# untitled.net
KiCad netlist of a schematic drawn in EAGLE
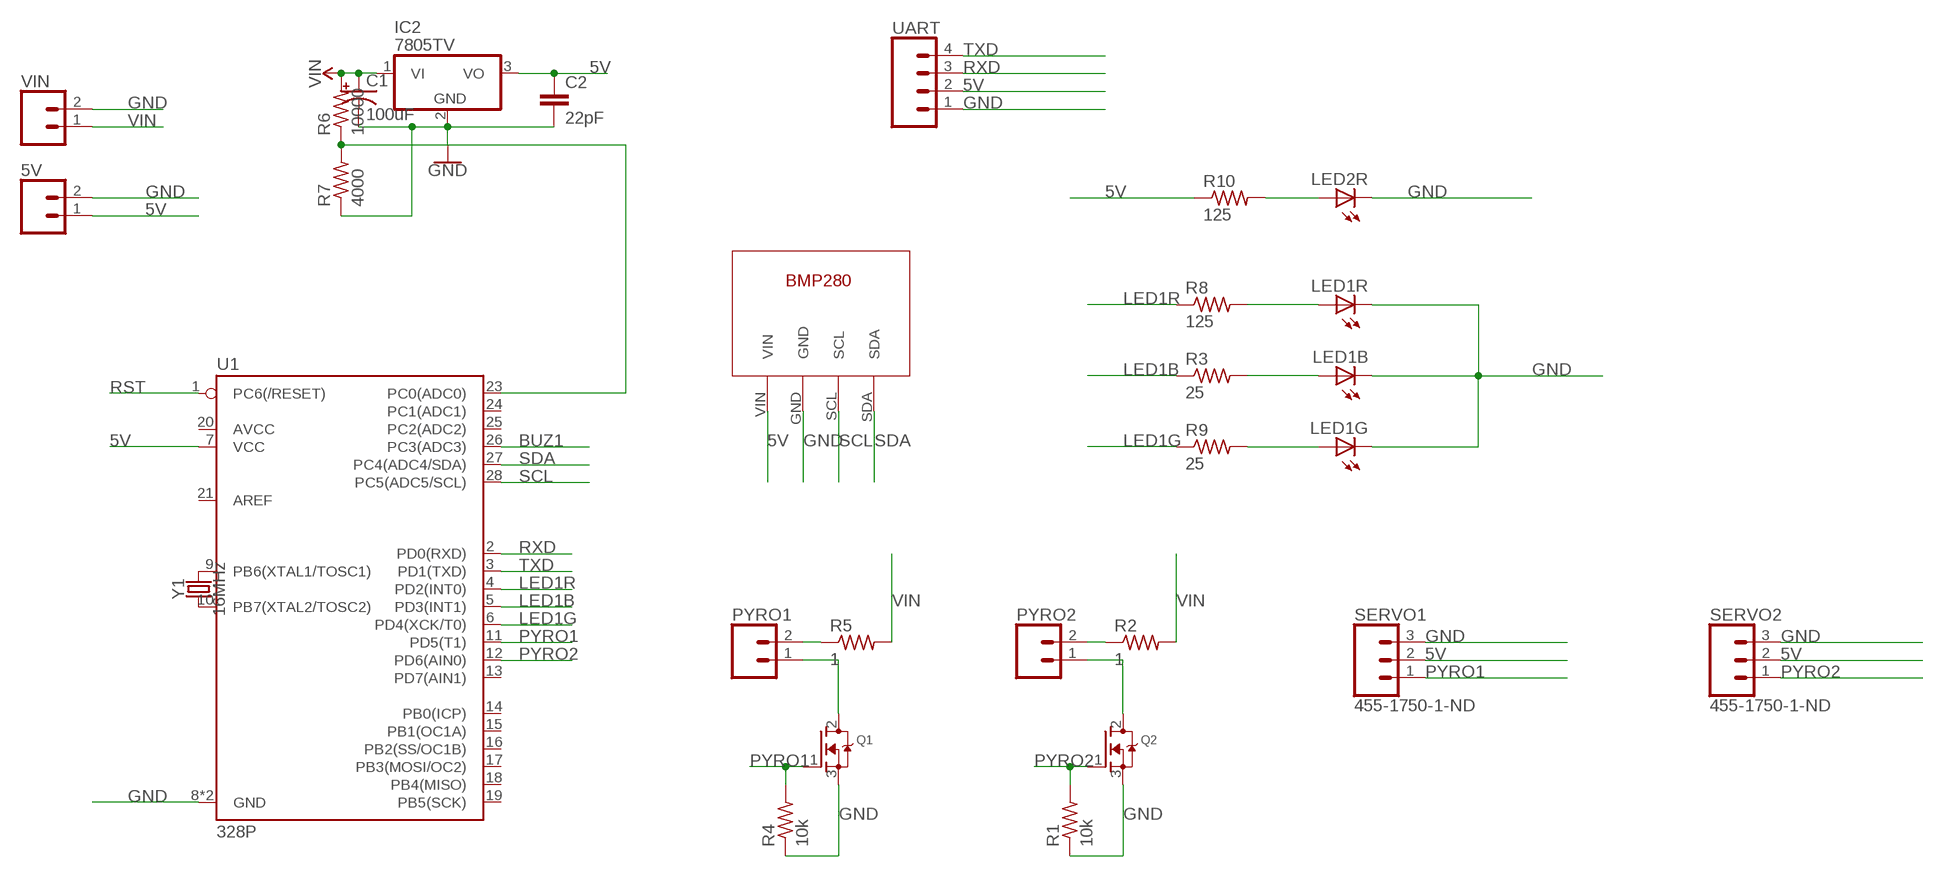
[diagram p0: schematic, sheet 1]

(export (version "E")
  (design (tool "Eeschema 10.0.6"))
  (components
    (comp (ref "5V")
      (value "CONN_02")
      (footprint "eagle-import:1X02")
      (libsource (lib "eagle-import") (part "CONN_02"))
    )
    (comp (ref "C1")
      (value "100uF")
      (footprint "eagle-import:CPOL-RADIAL-2.5MM-6.5MM")
      (libsource (lib "eagle-import") (part "100UF-POLAR-RADIAL-2.5MM-25V-20%"))
    )
    (comp (ref "C2")
      (value "22pF")
      (footprint "eagle-import:CAP-PTH-2.54")
      (libsource (lib "eagle-import") (part "22PF-PTH-2.54MM-200V-5%"))
    )
    (comp (ref "IC2")
      (value "7805TV")
      (footprint "eagle-import:TO220V")
      (libsource (lib "eagle-import") (part "78TV05"))
    )
    (comp (ref "LED1B")
      (value "LED1B")
      (footprint "eagle-import:LED5MM")
      (libsource (lib "eagle-import") (part "LED5MM"))
    )
    (comp (ref "LED1G")
      (value "LED1G")
      (footprint "eagle-import:LED5MM")
      (libsource (lib "eagle-import") (part "LED5MM"))
    )
    (comp (ref "LED1R")
      (value "LED1R")
      (footprint "eagle-import:LED5MM")
      (libsource (lib "eagle-import") (part "LED5MM"))
    )
    (comp (ref "LED2R")
      (value "LED1R")
      (footprint "eagle-import:LED5MM")
      (libsource (lib "eagle-import") (part "LED5MM"))
    )
    (comp (ref "PYRO1")
      (value "CONN_02")
      (footprint "eagle-import:1X02")
      (libsource (lib "eagle-import") (part "SparkFun-Connectors_513_CONN_02"))
    )
    (comp (ref "PYRO2")
      (value "CONN_02")
      (footprint "eagle-import:1X02")
      (libsource (lib "eagle-import") (part "SparkFun-Connectors_513_CONN_02"))
    )
    (comp (ref "Q1")
      (value "MOSFET-NGDS_TO220V")
      (footprint "eagle-import:TO220V")
      (libsource (lib "eagle-import") (part "MOSFET-NGDS_TO220V"))
    )
    (comp (ref "Q2")
      (value "MOSFET-NGDS_TO220V")
      (footprint "eagle-import:TO220V")
      (libsource (lib "eagle-import") (part "MOSFET-NGDS_TO220V"))
    )
    (comp (ref "R1")
      (value "10k")
      (footprint "eagle-import:0805-THM")
      (libsource (lib "eagle-import") (part "FLIPFLOP-RES"))
    )
    (comp (ref "R2")
      (value "1")
      (footprint "eagle-import:0805-THM")
      (libsource (lib "eagle-import") (part "FLIPFLOP-RES"))
    )
    (comp (ref "R3")
      (value "25")
      (footprint "eagle-import:0805-THM")
      (libsource (lib "eagle-import") (part "FLIPFLOP-RES"))
    )
    (comp (ref "R4")
      (value "10k")
      (footprint "eagle-import:0805-THM")
      (libsource (lib "eagle-import") (part "FLIPFLOP-RES"))
    )
    (comp (ref "R5")
      (value "1")
      (footprint "eagle-import:0805-THM")
      (libsource (lib "eagle-import") (part "FLIPFLOP-RES"))
    )
    (comp (ref "R6")
      (value "10000")
      (footprint "eagle-import:0805-THM")
      (libsource (lib "eagle-import") (part "FLIPFLOP-RES"))
    )
    (comp (ref "R7")
      (value "4000")
      (footprint "eagle-import:0805-THM")
      (libsource (lib "eagle-import") (part "FLIPFLOP-RES"))
    )
    (comp (ref "R8")
      (value "125")
      (footprint "eagle-import:0805-THM")
      (libsource (lib "eagle-import") (part "FLIPFLOP-RES"))
    )
    (comp (ref "R9")
      (value "25")
      (footprint "eagle-import:0805-THM")
      (libsource (lib "eagle-import") (part "FLIPFLOP-RES"))
    )
    (comp (ref "R10")
      (value "125")
      (footprint "eagle-import:0805-THM")
      (libsource (lib "eagle-import") (part "FLIPFLOP-RES"))
    )
    (comp (ref "SERVO1")
      (value "455-1750-1-ND")
      (footprint "eagle-import:1X03")
      (libsource (lib "eagle-import") (part "CONN_03"))
    )
    (comp (ref "SERVO2")
      (value "455-1750-1-ND")
      (footprint "eagle-import:1X03")
      (libsource (lib "eagle-import") (part "CONN_03"))
    )
    (comp (ref "U$1")
      (value "BMP280")
      (footprint "eagle-import:BMP280")
      (libsource (lib "eagle-import") (part "BMP280"))
    )
    (comp (ref "U1")
      (value "328P")
      (footprint "eagle-import:DIP28")
      (libsource (lib "eagle-import") (part "ATMEGA328P_PDIP"))
    )
    (comp (ref "UART")
      (value "CONN_04PTH")
      (footprint "eagle-import:1X04")
      (libsource (lib "eagle-import") (part "CONN_04PTH"))
    )
    (comp (ref "VIN")
      (value "CONN_02")
      (footprint "eagle-import:1X02")
      (libsource (lib "eagle-import") (part "CONN_02"))
    )
    (comp (ref "Y1")
      (value "16MHz")
      (footprint "eagle-import:HC49US")
      (libsource (lib "eagle-import") (part "CRYSTAL-16MHZPTH-HC49US"))
    )
  )
  (nets
    (net (code "1") (name "/5V") (class "Default")
      (node (ref "5V") (pin "1") (pinfunction "1_1") (pintype "passive"))
      (node (ref "C2") (pin "1") (pinfunction "1_1") (pintype "passive"))
      (node (ref "IC2") (pin "3") (pinfunction "VO_3") (pintype "passive"))
      (node (ref "R10") (pin "1") (pinfunction "1_1") (pintype "passive"))
      (node (ref "SERVO1") (pin "2") (pinfunction "2_2") (pintype "passive"))
      (node (ref "SERVO2") (pin "2") (pinfunction "2_2") (pintype "passive"))
      (node (ref "U$1") (pin "VIN") (pinfunction "VIN_VIN") (pintype "bidirectional"))
      (node (ref "U1") (pin "7") (pinfunction "VCC_7") (pintype "bidirectional"))
      (node (ref "UART") (pin "2") (pinfunction "2_2") (pintype "passive"))
    )
    (net (code "2") (name "/BUZ1") (class "Default")
      (node (ref "U1") (pin "26") (pinfunction "PC3(ADC3)_26") (pintype "bidirectional"))
    )
    (net (code "3") (name "/LED1B") (class "Default")
      (node (ref "R3") (pin "1") (pinfunction "1_1") (pintype "passive"))
      (node (ref "U1") (pin "5") (pinfunction "PD3(INT1)_5") (pintype "bidirectional"))
    )
    (net (code "4") (name "/LED1G") (class "Default")
      (node (ref "R9") (pin "1") (pinfunction "1_1") (pintype "passive"))
      (node (ref "U1") (pin "6") (pinfunction "PD4(XCK/T0)_6") (pintype "bidirectional"))
    )
    (net (code "5") (name "/LED1R") (class "Default")
      (node (ref "R8") (pin "1") (pinfunction "1_1") (pintype "passive"))
      (node (ref "U1") (pin "4") (pinfunction "PD2(INT0)_4") (pintype "bidirectional"))
    )
    (net (code "6") (name "/PYRO1") (class "Default")
      (node (ref "Q1") (pin "1") (pinfunction "G_1") (pintype "bidirectional"))
      (node (ref "R4") (pin "2") (pinfunction "2_2") (pintype "passive"))
      (node (ref "SERVO1") (pin "1") (pinfunction "1_1") (pintype "passive"))
      (node (ref "U1") (pin "11") (pinfunction "PD5(T1)_11") (pintype "bidirectional"))
    )
    (net (code "7") (name "/PYRO2") (class "Default")
      (node (ref "Q2") (pin "1") (pinfunction "G_1") (pintype "bidirectional"))
      (node (ref "R1") (pin "2") (pinfunction "2_2") (pintype "passive"))
      (node (ref "SERVO2") (pin "1") (pinfunction "1_1") (pintype "passive"))
      (node (ref "U1") (pin "12") (pinfunction "PD6(AIN0)_12") (pintype "bidirectional"))
    )
    (net (code "8") (name "/RST") (class "Default")
      (node (ref "U1") (pin "1") (pinfunction "PC6(/RESET)_1") (pintype "bidirectional"))
    )
    (net (code "9") (name "/RXD") (class "Default")
      (node (ref "U1") (pin "2") (pinfunction "PD0(RXD)_2") (pintype "bidirectional"))
      (node (ref "UART") (pin "3") (pinfunction "3_3") (pintype "passive"))
    )
    (net (code "10") (name "/SCL") (class "Default")
      (node (ref "U$1") (pin "SCL") (pinfunction "SCL_SCL") (pintype "bidirectional"))
      (node (ref "U1") (pin "28") (pinfunction "PC5(ADC5/SCL)_28") (pintype "bidirectional"))
    )
    (net (code "11") (name "/SDA") (class "Default")
      (node (ref "U$1") (pin "SDA") (pinfunction "SDA_SDA") (pintype "bidirectional"))
      (node (ref "U1") (pin "27") (pinfunction "PC4(ADC4/SDA)_27") (pintype "bidirectional"))
    )
    (net (code "12") (name "/TXD") (class "Default")
      (node (ref "U1") (pin "3") (pinfunction "PD1(TXD)_3") (pintype "bidirectional"))
      (node (ref "UART") (pin "4") (pinfunction "4_4") (pintype "passive"))
    )
    (net (code "13") (name "GND") (class "Default")
      (node (ref "5V") (pin "2") (pinfunction "2_2") (pintype "passive"))
      (node (ref "C1") (pin "2") (pinfunction "-_2") (pintype "passive"))
      (node (ref "C2") (pin "2") (pinfunction "2_2") (pintype "passive"))
      (node (ref "IC2") (pin "2") (pinfunction "GND_2") (pintype "passive"))
      (node (ref "LED1B") (pin "K") (pinfunction "C_K") (pintype "passive"))
      (node (ref "LED1G") (pin "K") (pinfunction "C_K") (pintype "passive"))
      (node (ref "LED1R") (pin "K") (pinfunction "C_K") (pintype "passive"))
      (node (ref "LED2R") (pin "K") (pinfunction "C_K") (pintype "passive"))
      (node (ref "Q1") (pin "3") (pinfunction "S_3") (pintype "bidirectional"))
      (node (ref "Q2") (pin "3") (pinfunction "S_3") (pintype "bidirectional"))
      (node (ref "R1") (pin "1") (pinfunction "1_1") (pintype "passive"))
      (node (ref "R4") (pin "1") (pinfunction "1_1") (pintype "passive"))
      (node (ref "R7") (pin "1") (pinfunction "1_1") (pintype "passive"))
      (node (ref "SERVO1") (pin "3") (pinfunction "3_3") (pintype "passive"))
      (node (ref "SERVO2") (pin "3") (pinfunction "3_3") (pintype "passive"))
      (node (ref "U$1") (pin "GND") (pinfunction "GND_GND") (pintype "bidirectional"))
      (node (ref "U1") (pin "22") (pinfunction "GND_22") (pintype "bidirectional"))
      (node (ref "U1") (pin "8") (pinfunction "GND_8") (pintype "bidirectional"))
      (node (ref "UART") (pin "1") (pinfunction "1_1") (pintype "passive"))
      (node (ref "VIN") (pin "2") (pinfunction "2_2") (pintype "passive"))
    )
    (net (code "14") (name "Net-(LED1B-PadA)") (class "Default")
      (node (ref "LED1B") (pin "A") (pinfunction "A_A") (pintype "passive"))
      (node (ref "R3") (pin "2") (pinfunction "2_2") (pintype "passive"))
    )
    (net (code "15") (name "Net-(LED1G-PadA)") (class "Default")
      (node (ref "LED1G") (pin "A") (pinfunction "A_A") (pintype "passive"))
      (node (ref "R9") (pin "2") (pinfunction "2_2") (pintype "passive"))
    )
    (net (code "16") (name "Net-(LED1R-PadA)") (class "Default")
      (node (ref "LED1R") (pin "A") (pinfunction "A_A") (pintype "passive"))
      (node (ref "R8") (pin "2") (pinfunction "2_2") (pintype "passive"))
    )
    (net (code "17") (name "Net-(LED2R-PadA)") (class "Default")
      (node (ref "LED2R") (pin "A") (pinfunction "A_A") (pintype "passive"))
      (node (ref "R10") (pin "2") (pinfunction "2_2") (pintype "passive"))
    )
    (net (code "18") (name "Net-(PYRO1-Pad2)") (class "Default")
      (node (ref "PYRO1") (pin "2") (pinfunction "2_2") (pintype "passive"))
      (node (ref "R5") (pin "1") (pinfunction "1_1") (pintype "passive"))
    )
    (net (code "19") (name "Net-(PYRO2-Pad2)") (class "Default")
      (node (ref "PYRO2") (pin "2") (pinfunction "2_2") (pintype "passive"))
      (node (ref "R2") (pin "1") (pinfunction "1_1") (pintype "passive"))
    )
    (net (code "20") (name "Net-(Q1-D)") (class "Default")
      (node (ref "PYRO1") (pin "1") (pinfunction "1_1") (pintype "passive"))
      (node (ref "Q1") (pin "2") (pinfunction "D_2") (pintype "bidirectional"))
    )
    (net (code "21") (name "Net-(Q2-D)") (class "Default")
      (node (ref "PYRO2") (pin "1") (pinfunction "1_1") (pintype "passive"))
      (node (ref "Q2") (pin "2") (pinfunction "D_2") (pintype "bidirectional"))
    )
    (net (code "22") (name "Net-(U1-PB6(XTAL1{slash}TOSC1))") (class "Default")
      (node (ref "U1") (pin "9") (pinfunction "PB6(XTAL1/TOSC1)_9") (pintype "bidirectional"))
      (node (ref "Y1") (pin "2") (pinfunction "2_2") (pintype "passive"))
    )
    (net (code "23") (name "Net-(U1-PB7(XTAL2{slash}TOSC2))") (class "Default")
      (node (ref "U1") (pin "10") (pinfunction "PB7(XTAL2/TOSC2)_10") (pintype "bidirectional"))
      (node (ref "Y1") (pin "1") (pinfunction "1_1") (pintype "passive"))
    )
    (net (code "24") (name "Net-(U1-PC0(ADC0))") (class "Default")
      (node (ref "R6") (pin "1") (pinfunction "1_1") (pintype "passive"))
      (node (ref "R7") (pin "2") (pinfunction "2_2") (pintype "passive"))
      (node (ref "U1") (pin "23") (pinfunction "PC0(ADC0)_23") (pintype "bidirectional"))
    )
    (net (code "25") (name "VIN") (class "Default")
      (node (ref "C1") (pin "1") (pinfunction "+_1") (pintype "passive"))
      (node (ref "IC2") (pin "1") (pinfunction "VI_1") (pintype "input"))
      (node (ref "R2") (pin "2") (pinfunction "2_2") (pintype "passive"))
      (node (ref "R5") (pin "2") (pinfunction "2_2") (pintype "passive"))
      (node (ref "R6") (pin "2") (pinfunction "2_2") (pintype "passive"))
      (node (ref "VIN") (pin "1") (pinfunction "1_1") (pintype "passive"))
    )
    (net (code "26") (name "unconnected-(U1-AREF-Pad21)") (class "Default")
      (node (ref "U1") (pin "21") (pinfunction "AREF_21") (pintype "bidirectional"))
    )
    (net (code "27") (name "unconnected-(U1-AVCC-Pad20)") (class "Default")
      (node (ref "U1") (pin "20") (pinfunction "AVCC_20") (pintype "bidirectional"))
    )
    (net (code "28") (name "unconnected-(U1-PB0(ICP)-Pad14)") (class "Default")
      (node (ref "U1") (pin "14") (pinfunction "PB0(ICP)_14") (pintype "bidirectional"))
    )
    (net (code "29") (name "unconnected-(U1-PB1(OC1A)-Pad15)") (class "Default")
      (node (ref "U1") (pin "15") (pinfunction "PB1(OC1A)_15") (pintype "bidirectional"))
    )
    (net (code "30") (name "unconnected-(U1-PB2(SS{slash}OC1B)-Pad16)") (class "Default")
      (node (ref "U1") (pin "16") (pinfunction "PB2(SS/OC1B)_16") (pintype "bidirectional"))
    )
    (net (code "31") (name "unconnected-(U1-PB3(MOSI{slash}OC2)-Pad17)") (class "Default")
      (node (ref "U1") (pin "17") (pinfunction "PB3(MOSI/OC2)_17") (pintype "bidirectional"))
    )
    (net (code "32") (name "unconnected-(U1-PB4(MISO)-Pad18)") (class "Default")
      (node (ref "U1") (pin "18") (pinfunction "PB4(MISO)_18") (pintype "bidirectional"))
    )
    (net (code "33") (name "unconnected-(U1-PB5(SCK)-Pad19)") (class "Default")
      (node (ref "U1") (pin "19") (pinfunction "PB5(SCK)_19") (pintype "bidirectional"))
    )
    (net (code "34") (name "unconnected-(U1-PC1(ADC1)-Pad24)") (class "Default")
      (node (ref "U1") (pin "24") (pinfunction "PC1(ADC1)_24") (pintype "bidirectional"))
    )
    (net (code "35") (name "unconnected-(U1-PC2(ADC2)-Pad25)") (class "Default")
      (node (ref "U1") (pin "25") (pinfunction "PC2(ADC2)_25") (pintype "bidirectional"))
    )
    (net (code "36") (name "unconnected-(U1-PD7(AIN1)-Pad13)") (class "Default")
      (node (ref "U1") (pin "13") (pinfunction "PD7(AIN1)_13") (pintype "bidirectional"))
    )
  )
)
